# Kart_1.net
KiCad netlist of a schematic drawn in EAGLE
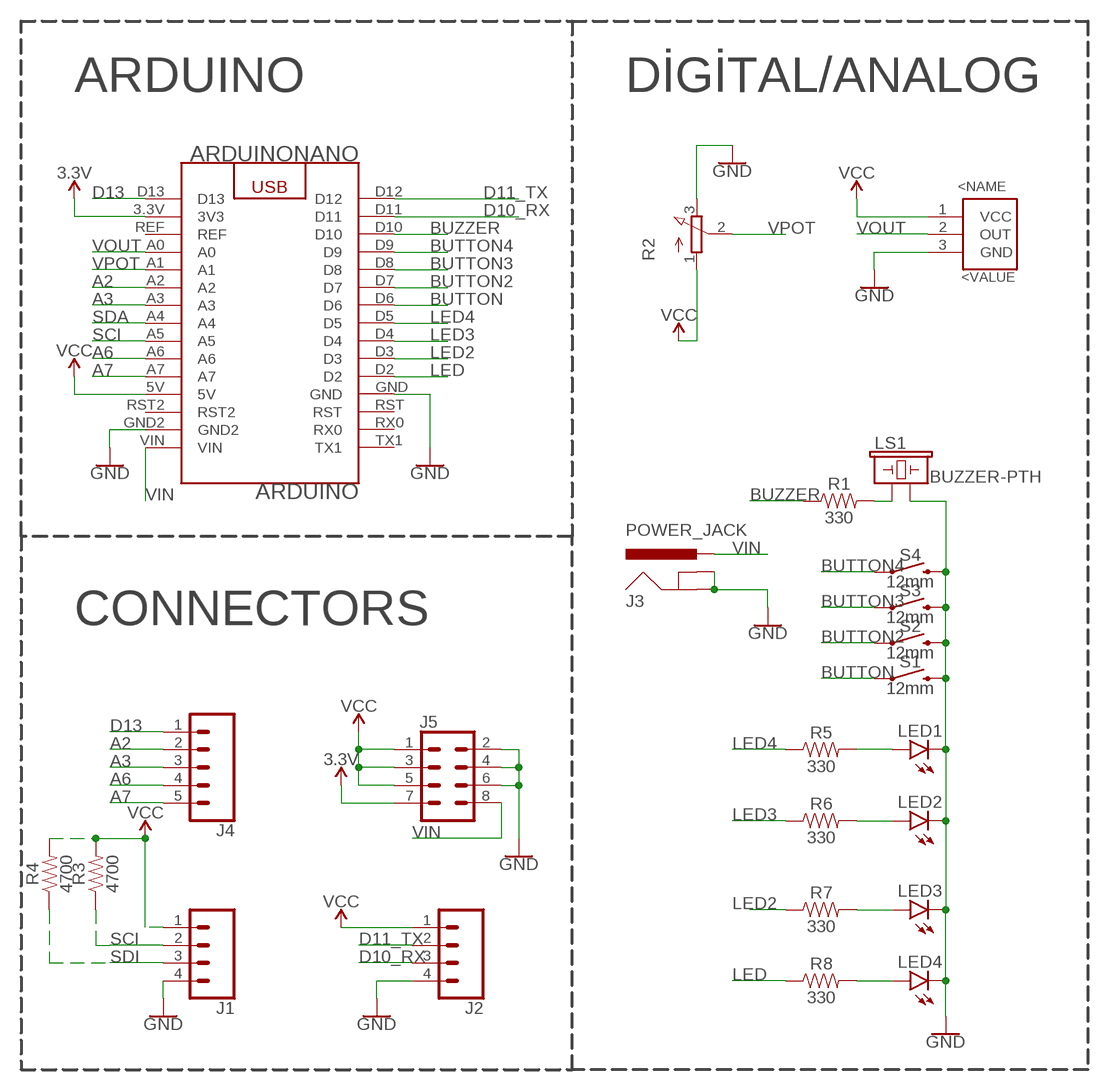
[diagram p0: schematic, sheet 1]

(export (version "E")
  (design (tool "Eeschema 10.0.6"))
  (components
    (comp (ref "ARDUINO")
      (value "ARDUINONANO")
      (footprint "eagle-import:ARDUINONANO")
      (libsource (lib "eagle-import") (part "ARDUINONANO"))
    )
    (comp (ref "J1")
      (value "CONN_04")
      (footprint "eagle-import:1X04")
      (libsource (lib "eagle-import") (part "CONN_04"))
    )
    (comp (ref "J2")
      (value "CONN_04")
      (footprint "eagle-import:1X04")
      (libsource (lib "eagle-import") (part "CONN_04"))
    )
    (comp (ref "J3")
      (value "POWER_JACK")
      (footprint "eagle-import:POWER_JACK_PTH")
      (libsource (lib "eagle-import") (part "POWER_JACK"))
    )
    (comp (ref "J4")
      (value "CONN_05")
      (footprint "eagle-import:1X05")
      (libsource (lib "eagle-import") (part "CONN_05"))
    )
    (comp (ref "J5")
      (value "CONN_04X2")
      (footprint "eagle-import:2X4")
      (libsource (lib "eagle-import") (part "CONN_04X2"))
    )
    (comp (ref "LED1")
      (value "LED3MM")
      (footprint "eagle-import:LED3MM")
      (libsource (lib "eagle-import") (part "LED3MM"))
    )
    (comp (ref "LED2")
      (value "LED3MM")
      (footprint "eagle-import:LED3MM")
      (libsource (lib "eagle-import") (part "LED3MM"))
    )
    (comp (ref "LED3")
      (value "LED3MM")
      (footprint "eagle-import:LED3MM")
      (libsource (lib "eagle-import") (part "LED3MM"))
    )
    (comp (ref "LED4")
      (value "LED3MM")
      (footprint "eagle-import:LED3MM")
      (libsource (lib "eagle-import") (part "LED3MM"))
    )
    (comp (ref "LM35")
      (value "LM35")
      (footprint "eagle-import:TO-92")
      (libsource (lib "eagle-import") (part "LM35"))
    )
    (comp (ref "LS1")
      (value "BUZZER-PTH")
      (footprint "eagle-import:BUZZER-12MM")
      (libsource (lib "eagle-import") (part "BUZZER-PTH"))
    )
    (comp (ref "R1")
      (value "330")
      (footprint "eagle-import:AXIAL-0.3")
      (libsource (lib "eagle-import") (part "10MOHM-HORIZ-1/4W-5%"))
    )
    (comp (ref "R2")
      (value "3RP/1610N")
      (footprint "eagle-import:3RP_1610N")
      (libsource (lib "eagle-import") (part "3RP/1610N"))
    )
    (comp (ref "R3")
      (value "4700")
      (footprint "eagle-import:AXIAL-0.3")
      (libsource (lib "eagle-import") (part "10MOHM-HORIZ-1/4W-5%"))
    )
    (comp (ref "R4")
      (value "4700")
      (footprint "eagle-import:AXIAL-0.3")
      (libsource (lib "eagle-import") (part "10MOHM-HORIZ-1/4W-5%"))
    )
    (comp (ref "R5")
      (value "330")
      (footprint "eagle-import:AXIAL-0.3")
      (libsource (lib "eagle-import") (part "10MOHM-HORIZ-1/4W-5%"))
    )
    (comp (ref "R6")
      (value "330")
      (footprint "eagle-import:AXIAL-0.3")
      (libsource (lib "eagle-import") (part "10MOHM-HORIZ-1/4W-5%"))
    )
    (comp (ref "R7")
      (value "330")
      (footprint "eagle-import:AXIAL-0.3")
      (libsource (lib "eagle-import") (part "10MOHM-HORIZ-1/4W-5%"))
    )
    (comp (ref "R8")
      (value "330")
      (footprint "eagle-import:AXIAL-0.3")
      (libsource (lib "eagle-import") (part "10MOHM-HORIZ-1/4W-5%"))
    )
    (comp (ref "S1")
      (value "12mm")
      (footprint "eagle-import:TACTILE_SWITCH_PTH_12MM")
      (libsource (lib "eagle-import") (part "MOMENTARY-SWITCH-SPST-PTH-12MM"))
    )
    (comp (ref "S2")
      (value "12mm")
      (footprint "eagle-import:TACTILE_SWITCH_PTH_12MM")
      (libsource (lib "eagle-import") (part "MOMENTARY-SWITCH-SPST-PTH-12MM"))
    )
    (comp (ref "S3")
      (value "12mm")
      (footprint "eagle-import:TACTILE_SWITCH_PTH_12MM")
      (libsource (lib "eagle-import") (part "MOMENTARY-SWITCH-SPST-PTH-12MM"))
    )
    (comp (ref "S4")
      (value "12mm")
      (footprint "eagle-import:TACTILE_SWITCH_PTH_12MM")
      (libsource (lib "eagle-import") (part "MOMENTARY-SWITCH-SPST-PTH-12MM"))
    )
  )
  (nets
    (net (code "1") (name "/A2") (class "Default")
      (node (ref "ARDUINO") (pin "A2") (pinfunction "A2_A2") (pintype "bidirectional"))
      (node (ref "J4") (pin "2") (pinfunction "2_2") (pintype "passive"))
    )
    (net (code "2") (name "/A3") (class "Default")
      (node (ref "ARDUINO") (pin "A3") (pinfunction "A3_A3") (pintype "bidirectional"))
      (node (ref "J4") (pin "3") (pinfunction "3_3") (pintype "passive"))
    )
    (net (code "3") (name "/A6") (class "Default")
      (node (ref "ARDUINO") (pin "A6") (pinfunction "A6_A6") (pintype "bidirectional"))
      (node (ref "J4") (pin "4") (pinfunction "4_4") (pintype "passive"))
    )
    (net (code "4") (name "/A7") (class "Default")
      (node (ref "ARDUINO") (pin "A7") (pinfunction "A7_A7") (pintype "bidirectional"))
      (node (ref "J4") (pin "5") (pinfunction "5_5") (pintype "passive"))
    )
    (net (code "5") (name "/BUTTON") (class "Default")
      (node (ref "ARDUINO") (pin "D6") (pinfunction "D6_D6") (pintype "bidirectional"))
      (node (ref "S1") (pin "1") (pinfunction "1_1") (pintype "passive"))
    )
    (net (code "6") (name "/BUTTON2") (class "Default")
      (node (ref "ARDUINO") (pin "D7") (pinfunction "D7_D7") (pintype "bidirectional"))
      (node (ref "S2") (pin "1") (pinfunction "1_1") (pintype "passive"))
    )
    (net (code "7") (name "/BUTTON3") (class "Default")
      (node (ref "ARDUINO") (pin "D8") (pinfunction "D8_D8") (pintype "bidirectional"))
      (node (ref "S3") (pin "1") (pinfunction "1_1") (pintype "passive"))
    )
    (net (code "8") (name "/BUTTON4") (class "Default")
      (node (ref "ARDUINO") (pin "D9") (pinfunction "D9_D9") (pintype "bidirectional"))
      (node (ref "S4") (pin "1") (pinfunction "1_1") (pintype "passive"))
    )
    (net (code "9") (name "/BUZZER") (class "Default")
      (node (ref "ARDUINO") (pin "D10") (pinfunction "D10_D10") (pintype "bidirectional"))
      (node (ref "R1") (pin "P$1") (pinfunction "1_P$1") (pintype "passive"))
    )
    (net (code "10") (name "/D10_RX") (class "Default")
      (node (ref "ARDUINO") (pin "D11") (pinfunction "D11_D11") (pintype "bidirectional"))
      (node (ref "J2") (pin "3") (pinfunction "3_3") (pintype "passive"))
    )
    (net (code "11") (name "/D11_TX") (class "Default")
      (node (ref "ARDUINO") (pin "D12") (pinfunction "D12_D12") (pintype "bidirectional"))
      (node (ref "J2") (pin "2") (pinfunction "2_2") (pintype "passive"))
    )
    (net (code "12") (name "/D13") (class "Default")
      (node (ref "ARDUINO") (pin "D13") (pinfunction "D13_D13") (pintype "bidirectional"))
      (node (ref "J4") (pin "1") (pinfunction "1_1") (pintype "passive"))
    )
    (net (code "13") (name "/LED") (class "Default")
      (node (ref "ARDUINO") (pin "D2") (pinfunction "D2_D2") (pintype "bidirectional"))
      (node (ref "R8") (pin "P$1") (pinfunction "1_P$1") (pintype "passive"))
    )
    (net (code "14") (name "/LED2") (class "Default")
      (node (ref "ARDUINO") (pin "D3") (pinfunction "D3_D3") (pintype "bidirectional"))
      (node (ref "R7") (pin "P$1") (pinfunction "1_P$1") (pintype "passive"))
    )
    (net (code "15") (name "/LED3") (class "Default")
      (node (ref "ARDUINO") (pin "D4") (pinfunction "D4_D4") (pintype "bidirectional"))
      (node (ref "R6") (pin "P$1") (pinfunction "1_P$1") (pintype "passive"))
    )
    (net (code "16") (name "/LED4") (class "Default")
      (node (ref "ARDUINO") (pin "D5") (pinfunction "D5_D5") (pintype "bidirectional"))
      (node (ref "R5") (pin "P$1") (pinfunction "1_P$1") (pintype "passive"))
    )
    (net (code "17") (name "/SCI") (class "Default")
      (node (ref "ARDUINO") (pin "A5") (pinfunction "A5_A5") (pintype "bidirectional"))
      (node (ref "J1") (pin "2") (pinfunction "2_2") (pintype "passive"))
      (node (ref "R3") (pin "P$1") (pinfunction "1_P$1") (pintype "passive"))
    )
    (net (code "18") (name "/SDA") (class "Default")
      (node (ref "ARDUINO") (pin "A4") (pinfunction "A4_A4") (pintype "bidirectional"))
    )
    (net (code "19") (name "/SDI") (class "Default")
      (node (ref "J1") (pin "3") (pinfunction "3_3") (pintype "passive"))
      (node (ref "R4") (pin "P$1") (pinfunction "1_P$1") (pintype "passive"))
    )
    (net (code "20") (name "/VIN") (class "Default")
      (node (ref "ARDUINO") (pin "VIN") (pinfunction "VIN_VIN") (pintype "bidirectional"))
      (node (ref "J3") (pin "PWR") (pinfunction "PWR_PWR") (pintype "bidirectional"))
      (node (ref "J5") (pin "8") (pinfunction "8_8") (pintype "passive"))
    )
    (net (code "21") (name "/VOUT") (class "Default")
      (node (ref "ARDUINO") (pin "A0") (pinfunction "A0_A0") (pintype "bidirectional"))
      (node (ref "LM35") (pin "2") (pinfunction "OUT_2") (pintype "bidirectional"))
    )
    (net (code "22") (name "/VPOT") (class "Default")
      (node (ref "ARDUINO") (pin "A1") (pinfunction "A1_A1") (pintype "bidirectional"))
      (node (ref "R2") (pin "2") (pinfunction "S_2") (pintype "passive"))
    )
    (net (code "23") (name "3.3V") (class "Default")
      (node (ref "ARDUINO") (pin "3.3V") (pinfunction "3V3_3.3V") (pintype "bidirectional"))
      (node (ref "J5") (pin "7") (pinfunction "7_7") (pintype "passive"))
    )
    (net (code "24") (name "GND") (class "Default")
      (node (ref "ARDUINO") (pin "GND") (pinfunction "GND_GND") (pintype "bidirectional"))
      (node (ref "ARDUINO") (pin "GND2") (pinfunction "GND2_GND2") (pintype "bidirectional"))
      (node (ref "J1") (pin "4") (pinfunction "4_4") (pintype "passive"))
      (node (ref "J2") (pin "4") (pinfunction "4_4") (pintype "passive"))
      (node (ref "J3") (pin "GND") (pinfunction "GND_GND") (pintype "bidirectional"))
      (node (ref "J3") (pin "GNDBREAK") (pinfunction "GNDBREAK_GNDBREAK") (pintype "bidirectional"))
      (node (ref "J5") (pin "2") (pinfunction "2_2") (pintype "passive"))
      (node (ref "J5") (pin "4") (pinfunction "4_4") (pintype "passive"))
      (node (ref "J5") (pin "6") (pinfunction "6_6") (pintype "passive"))
      (node (ref "LED1") (pin "K") (pinfunction "C_K") (pintype "passive"))
      (node (ref "LED2") (pin "K") (pinfunction "C_K") (pintype "passive"))
      (node (ref "LED3") (pin "K") (pinfunction "C_K") (pintype "passive"))
      (node (ref "LED4") (pin "K") (pinfunction "C_K") (pintype "passive"))
      (node (ref "LM35") (pin "3") (pinfunction "GND_3") (pintype "bidirectional"))
      (node (ref "LS1") (pin "-") (pinfunction "2_-") (pintype "passive"))
      (node (ref "R2") (pin "3") (pinfunction "E_3") (pintype "passive"))
      (node (ref "S1") (pin "3") (pinfunction "2_3") (pintype "passive"))
      (node (ref "S2") (pin "3") (pinfunction "2_3") (pintype "passive"))
      (node (ref "S3") (pin "3") (pinfunction "2_3") (pintype "passive"))
      (node (ref "S4") (pin "3") (pinfunction "2_3") (pintype "passive"))
    )
    (net (code "25") (name "Net-(LS1-1)") (class "Default")
      (node (ref "LS1") (pin "+") (pinfunction "1_+") (pintype "passive"))
      (node (ref "R1") (pin "P$2") (pinfunction "2_P$2") (pintype "passive"))
    )
    (net (code "26") (name "Net-(R5-2)") (class "Default")
      (node (ref "LED1") (pin "A") (pinfunction "A_A") (pintype "passive"))
      (node (ref "R5") (pin "P$2") (pinfunction "2_P$2") (pintype "passive"))
    )
    (net (code "27") (name "Net-(R6-2)") (class "Default")
      (node (ref "LED2") (pin "A") (pinfunction "A_A") (pintype "passive"))
      (node (ref "R6") (pin "P$2") (pinfunction "2_P$2") (pintype "passive"))
    )
    (net (code "28") (name "Net-(R7-2)") (class "Default")
      (node (ref "LED3") (pin "A") (pinfunction "A_A") (pintype "passive"))
      (node (ref "R7") (pin "P$2") (pinfunction "2_P$2") (pintype "passive"))
    )
    (net (code "29") (name "Net-(R8-2)") (class "Default")
      (node (ref "LED4") (pin "A") (pinfunction "A_A") (pintype "passive"))
      (node (ref "R8") (pin "P$2") (pinfunction "2_P$2") (pintype "passive"))
    )
    (net (code "30") (name "VCC") (class "Default")
      (node (ref "ARDUINO") (pin "5V") (pinfunction "5V_5V") (pintype "bidirectional"))
      (node (ref "J1") (pin "1") (pinfunction "1_1") (pintype "passive"))
      (node (ref "J2") (pin "1") (pinfunction "1_1") (pintype "passive"))
      (node (ref "J5") (pin "1") (pinfunction "1_1") (pintype "passive"))
      (node (ref "J5") (pin "3") (pinfunction "3_3") (pintype "passive"))
      (node (ref "J5") (pin "5") (pinfunction "5_5") (pintype "passive"))
      (node (ref "LM35") (pin "1") (pinfunction "VCC_1") (pintype "bidirectional"))
      (node (ref "R2") (pin "1") (pinfunction "A_1") (pintype "passive"))
      (node (ref "R3") (pin "P$2") (pinfunction "2_P$2") (pintype "passive"))
      (node (ref "R4") (pin "P$2") (pinfunction "2_P$2") (pintype "passive"))
    )
    (net (code "31") (name "unconnected-(ARDUINO-PadREF)") (class "Default")
      (node (ref "ARDUINO") (pin "REF") (pinfunction "REF_REF") (pintype "bidirectional"))
    )
    (net (code "32") (name "unconnected-(ARDUINO-PadRST)") (class "Default")
      (node (ref "ARDUINO") (pin "RST") (pinfunction "RST_RST") (pintype "bidirectional"))
    )
    (net (code "33") (name "unconnected-(ARDUINO-PadRST2)") (class "Default")
      (node (ref "ARDUINO") (pin "RST2") (pinfunction "RST2_RST2") (pintype "bidirectional"))
    )
    (net (code "34") (name "unconnected-(ARDUINO-PadRX0)") (class "Default")
      (node (ref "ARDUINO") (pin "RX0") (pinfunction "RX0_RX0") (pintype "bidirectional"))
    )
    (net (code "35") (name "unconnected-(ARDUINO-PadTX1)") (class "Default")
      (node (ref "ARDUINO") (pin "TX1") (pinfunction "TX1_TX1") (pintype "bidirectional"))
    )
  )
)
